# joyAnalog.net
KiCad netlist of a schematic drawn in EAGLE
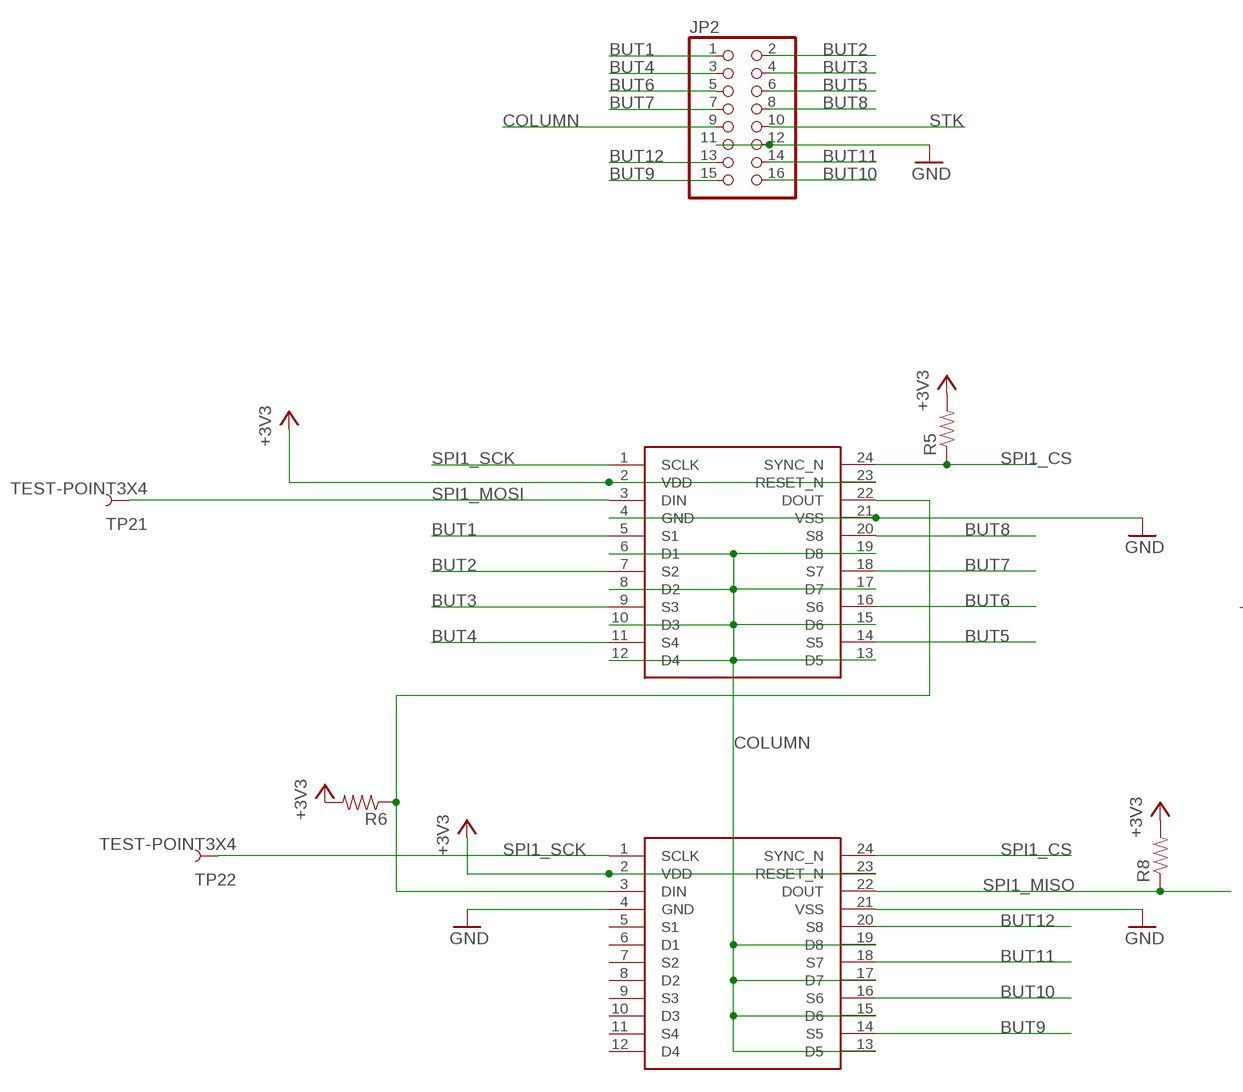
[diagram p0: schematic, sheet 1, part 1 of 2]
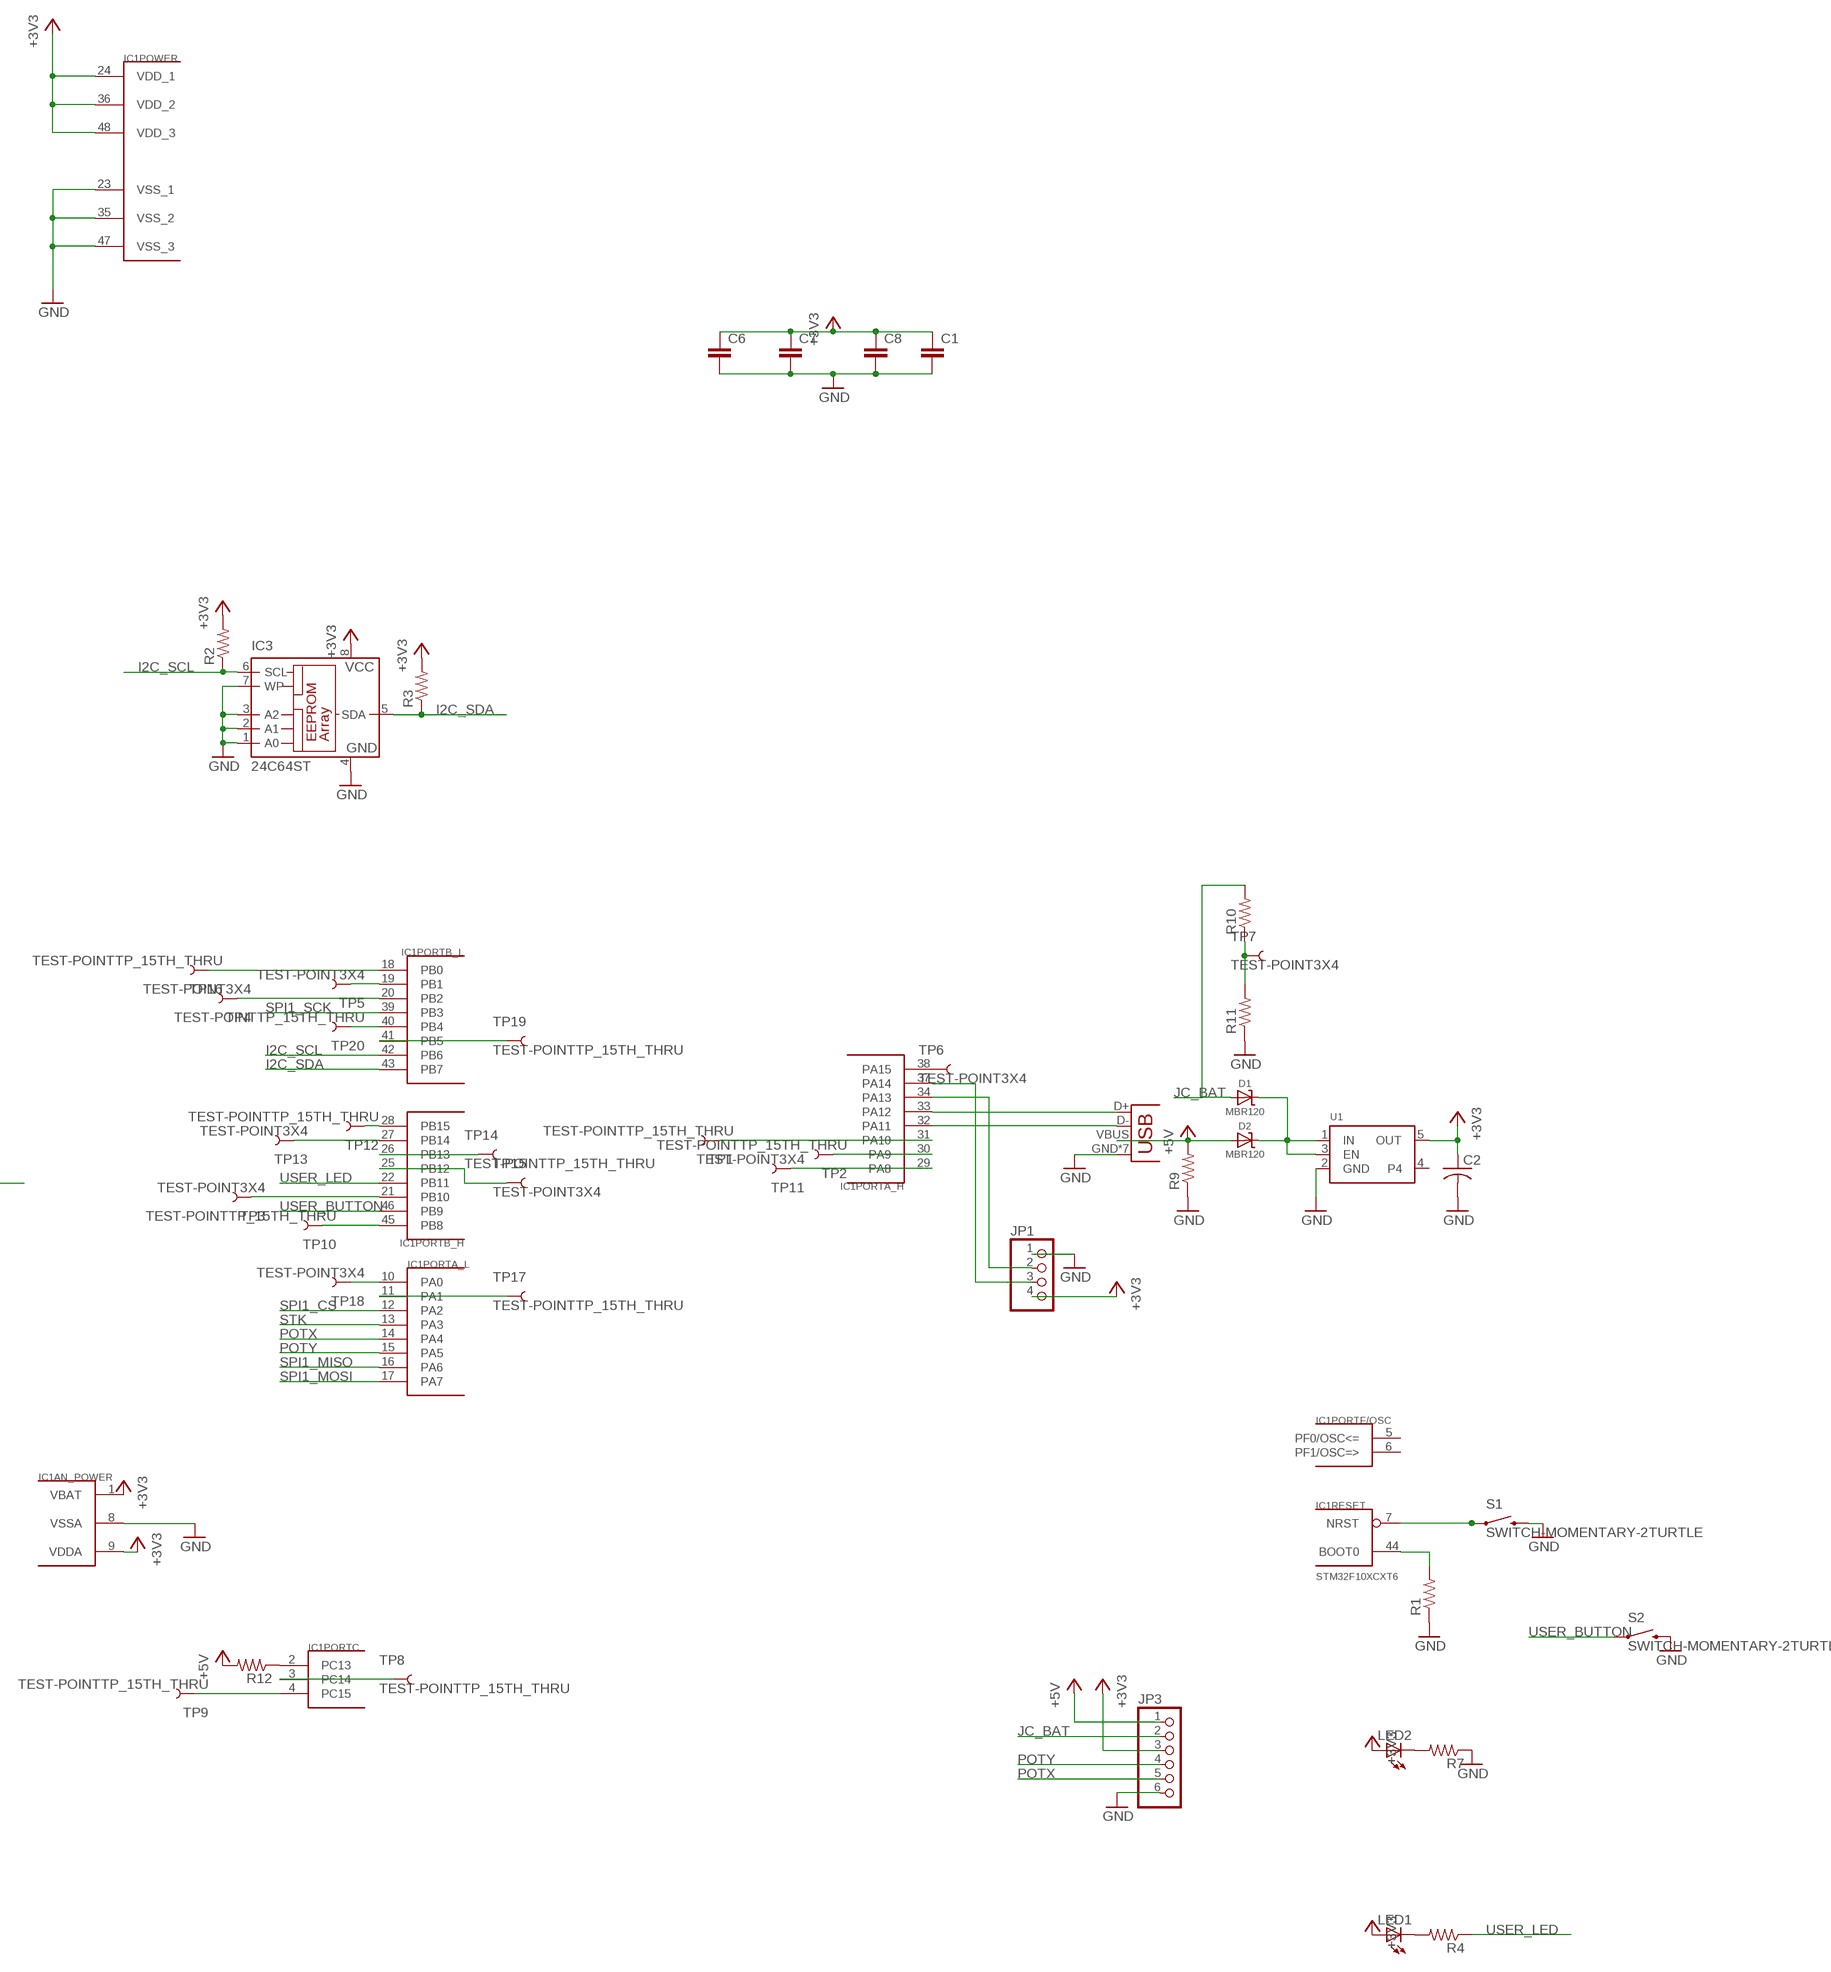
[diagram p1: schematic, sheet 1, part 2 of 2]

(export (version "E")
  (design (tool "Eeschema 10.0.6"))
  (components
    (comp (ref "C1")
      (value "CAP0805")
      (footprint "eagle-import:0805")
      (libsource (lib "eagle-import") (part "CAP0805"))
    )
    (comp (ref "C2")
      (value "C-USC1210")
      (footprint "eagle-import:C1210")
      (libsource (lib "eagle-import") (part "C-USC1210"))
    )
    (comp (ref "C6")
      (value "CAP0805")
      (footprint "eagle-import:0805")
      (libsource (lib "eagle-import") (part "CAP0805"))
    )
    (comp (ref "C7")
      (value "CAP0805")
      (footprint "eagle-import:0805")
      (libsource (lib "eagle-import") (part "CAP0805"))
    )
    (comp (ref "C8")
      (value "CAP0805")
      (footprint "eagle-import:0805")
      (libsource (lib "eagle-import") (part "CAP0805"))
    )
    (comp (ref "D1")
      (value "MBR120")
      (footprint "eagle-import:SOD-123")
      (libsource (lib "eagle-import") (part "DIODE-SCHOTTKYSOD-123"))
    )
    (comp (ref "D2")
      (value "MBR120")
      (footprint "eagle-import:SOD-123")
      (libsource (lib "eagle-import") (part "DIODE-SCHOTTKYSOD-123"))
    )
    (comp (ref "IC1")
      (value "STM32F10XCXT6")
      (footprint "eagle-import:TQFP48")
      (libsource (lib "eagle-import") (part "STM32F10XCXT6"))
    )
    (comp (ref "IC3")
      (value "24C64ST")
      (footprint "eagle-import:TSSOP8")
      (fields (field (name "MPN") "CAT24C64YI-GT3"))
      (libsource (lib "eagle-import") (part "24STC64"))
    )
    (comp (ref "JP1")
      (value "PINHD-1X4")
      (footprint "eagle-import:1X04")
      (libsource (lib "eagle-import") (part "PINHD-1X4"))
    )
    (comp (ref "JP2")
      (value "PINHD-2X8")
      (footprint "eagle-import:2X08")
      (libsource (lib "eagle-import") (part "PINHD-2X8"))
    )
    (comp (ref "JP3")
      (value "PINHD-1X6CB")
      (footprint "eagle-import:1X06-CLEANBIG")
      (libsource (lib "eagle-import") (part "PINHD-1X6CB"))
    )
    (comp (ref "LED1")
      (value "LEDCHIP-LED0805")
      (footprint "eagle-import:CHIP-LED0805")
      (libsource (lib "eagle-import") (part "LEDCHIP-LED0805"))
    )
    (comp (ref "LED2")
      (value "LEDCHIP-LED0805")
      (footprint "eagle-import:CHIP-LED0805")
      (libsource (lib "eagle-import") (part "LEDCHIP-LED0805"))
    )
    (comp (ref "R1")
      (value "RESISTOR0805-RES")
      (footprint "eagle-import:0805")
      (libsource (lib "eagle-import") (part "RESISTOR0805-RES"))
    )
    (comp (ref "R2")
      (value "RESISTOR0805-RES")
      (footprint "eagle-import:0805")
      (libsource (lib "eagle-import") (part "RESISTOR0805-RES"))
    )
    (comp (ref "R3")
      (value "RESISTOR0805-RES")
      (footprint "eagle-import:0805")
      (libsource (lib "eagle-import") (part "RESISTOR0805-RES"))
    )
    (comp (ref "R4")
      (value "RESISTOR0805-RES")
      (footprint "eagle-import:0805")
      (libsource (lib "eagle-import") (part "RESISTOR0805-RES"))
    )
    (comp (ref "R5")
      (value "RESISTOR0805-RES")
      (footprint "eagle-import:0805")
      (libsource (lib "eagle-import") (part "RESISTOR0805-RES"))
    )
    (comp (ref "R6")
      (value "RESISTOR0805-RES")
      (footprint "eagle-import:0805")
      (libsource (lib "eagle-import") (part "RESISTOR0805-RES"))
    )
    (comp (ref "R7")
      (value "RESISTOR0805-RES")
      (footprint "eagle-import:0805")
      (libsource (lib "eagle-import") (part "RESISTOR0805-RES"))
    )
    (comp (ref "R8")
      (value "RESISTOR0805-RES")
      (footprint "eagle-import:0805")
      (libsource (lib "eagle-import") (part "RESISTOR0805-RES"))
    )
    (comp (ref "R9")
      (value "RESISTOR0805-RES")
      (footprint "eagle-import:0805")
      (libsource (lib "eagle-import") (part "RESISTOR0805-RES"))
    )
    (comp (ref "R10")
      (value "RESISTOR0805-RES")
      (footprint "eagle-import:0805")
      (libsource (lib "eagle-import") (part "RESISTOR0805-RES"))
    )
    (comp (ref "R11")
      (value "RESISTOR0805-RES")
      (footprint "eagle-import:0805")
      (libsource (lib "eagle-import") (part "RESISTOR0805-RES"))
    )
    (comp (ref "R12")
      (value "RESISTOR0805-RES")
      (footprint "eagle-import:0805")
      (libsource (lib "eagle-import") (part "RESISTOR0805-RES"))
    )
    (comp (ref "S1")
      (value "SWITCH-MOMENTARY-2TURTLE")
      (footprint "eagle-import:KMR2")
      (libsource (lib "eagle-import") (part "SWITCH-MOMENTARY-2TURTLE"))
    )
    (comp (ref "S2")
      (value "SWITCH-MOMENTARY-2TURTLE")
      (footprint "eagle-import:KMR2")
      (libsource (lib "eagle-import") (part "SWITCH-MOMENTARY-2TURTLE"))
    )
    (comp (ref "TP1")
      (value "TEST-POINTTP_15TH_THRU")
      (footprint "eagle-import:TP_15TH")
      (libsource (lib "eagle-import") (part "pth testpoint_TEST-POINTTP_15TH_THRU"))
    )
    (comp (ref "TP2")
      (value "TEST-POINTTP_15TH_THRU")
      (footprint "eagle-import:TP_15TH")
      (libsource (lib "eagle-import") (part "pth testpoint_TEST-POINTTP_15TH_THRU"))
    )
    (comp (ref "TP3")
      (value "TEST-POINT3X4")
      (footprint "eagle-import:PAD.03X.04")
      (libsource (lib "eagle-import") (part "TEST-POINT3X4"))
    )
    (comp (ref "TP4")
      (value "TEST-POINT3X4")
      (footprint "eagle-import:PAD.03X.04")
      (libsource (lib "eagle-import") (part "TEST-POINT3X4"))
    )
    (comp (ref "TP5")
      (value "TEST-POINT3X4")
      (footprint "eagle-import:PAD.03X.04")
      (libsource (lib "eagle-import") (part "TEST-POINT3X4"))
    )
    (comp (ref "TP6")
      (value "TEST-POINT3X4")
      (footprint "eagle-import:PAD.03X.04")
      (libsource (lib "eagle-import") (part "TEST-POINT3X4"))
    )
    (comp (ref "TP7")
      (value "TEST-POINT3X4")
      (footprint "eagle-import:PAD.03X.04")
      (libsource (lib "eagle-import") (part "TEST-POINT3X4"))
    )
    (comp (ref "TP8")
      (value "TEST-POINTTP_15TH_THRU")
      (footprint "eagle-import:TP_15TH")
      (libsource (lib "eagle-import") (part "pth testpoint_TEST-POINTTP_15TH_THRU"))
    )
    (comp (ref "TP9")
      (value "TEST-POINTTP_15TH_THRU")
      (footprint "eagle-import:TP_15TH")
      (libsource (lib "eagle-import") (part "pth testpoint_TEST-POINTTP_15TH_THRU"))
    )
    (comp (ref "TP10")
      (value "TEST-POINTTP_15TH_THRU")
      (footprint "eagle-import:TP_15TH")
      (libsource (lib "eagle-import") (part "pth testpoint_TEST-POINTTP_15TH_THRU"))
    )
    (comp (ref "TP11")
      (value "TEST-POINT3X4")
      (footprint "eagle-import:PAD.03X.04")
      (libsource (lib "eagle-import") (part "TEST-POINT3X4"))
    )
    (comp (ref "TP12")
      (value "TEST-POINTTP_15TH_THRU")
      (footprint "eagle-import:TP_15TH")
      (libsource (lib "eagle-import") (part "pth testpoint_TEST-POINTTP_15TH_THRU"))
    )
    (comp (ref "TP13")
      (value "TEST-POINT3X4")
      (footprint "eagle-import:PAD.03X.04")
      (libsource (lib "eagle-import") (part "TEST-POINT3X4"))
    )
    (comp (ref "TP14")
      (value "TEST-POINTTP_15TH_THRU")
      (footprint "eagle-import:TP_15TH")
      (libsource (lib "eagle-import") (part "pth testpoint_TEST-POINTTP_15TH_THRU"))
    )
    (comp (ref "TP15")
      (value "TEST-POINT3X4")
      (footprint "eagle-import:PAD.03X.04")
      (libsource (lib "eagle-import") (part "TEST-POINT3X4"))
    )
    (comp (ref "TP16")
      (value "TEST-POINTTP_15TH_THRU")
      (footprint "eagle-import:TP_15TH")
      (libsource (lib "eagle-import") (part "pth testpoint_TEST-POINTTP_15TH_THRU"))
    )
    (comp (ref "TP17")
      (value "TEST-POINTTP_15TH_THRU")
      (footprint "eagle-import:TP_15TH")
      (libsource (lib "eagle-import") (part "pth testpoint_TEST-POINTTP_15TH_THRU"))
    )
    (comp (ref "TP18")
      (value "TEST-POINT3X4")
      (footprint "eagle-import:PAD.03X.04")
      (libsource (lib "eagle-import") (part "TEST-POINT3X4"))
    )
    (comp (ref "TP19")
      (value "TEST-POINTTP_15TH_THRU")
      (footprint "eagle-import:TP_15TH")
      (libsource (lib "eagle-import") (part "pth testpoint_TEST-POINTTP_15TH_THRU"))
    )
    (comp (ref "TP20")
      (value "TEST-POINTTP_15TH_THRU")
      (footprint "eagle-import:TP_15TH")
      (libsource (lib "eagle-import") (part "pth testpoint_TEST-POINTTP_15TH_THRU"))
    )
    (comp (ref "TP21")
      (value "TEST-POINT3X4")
      (footprint "eagle-import:PAD.03X.04")
      (libsource (lib "eagle-import") (part "TEST-POINT3X4"))
    )
    (comp (ref "TP22")
      (value "TEST-POINT3X4")
      (footprint "eagle-import:PAD.03X.04")
      (libsource (lib "eagle-import") (part "TEST-POINT3X4"))
    )
    (comp (ref "U$3")
      (value "ADG714_DEV")
      (footprint "eagle-import:TSSOP-24")
      (libsource (lib "eagle-import") (part "ADG714_DEV"))
    )
    (comp (ref "U$4")
      (value "ADG714_DEV")
      (footprint "eagle-import:TSSOP-24")
      (libsource (lib "eagle-import") (part "ADG714_DEV"))
    )
    (comp (ref "U1")
      (value "VREG_SOT23-5")
      (footprint "eagle-import:SOT23-5")
      (libsource (lib "eagle-import") (part "VREG_SOT23-5"))
    )
    (comp (ref "X1")
      (value "USB-MICROB")
      (footprint "eagle-import:USB-MICROB")
      (libsource (lib "eagle-import") (part "USB-MICROB"))
    )
  )
  (nets
    (net (code "1") (name "+3V3") (class "Default")
      (node (ref "C1") (pin "1") (pinfunction "1_1") (pintype "passive"))
      (node (ref "C2") (pin "1") (pinfunction "1_1") (pintype "passive"))
      (node (ref "C6") (pin "1") (pinfunction "1_1") (pintype "passive"))
      (node (ref "C7") (pin "1") (pinfunction "1_1") (pintype "passive"))
      (node (ref "C8") (pin "1") (pinfunction "1_1") (pintype "passive"))
      (node (ref "IC1") (pin "1") (pinfunction "VBAT_1") (pintype "power_in"))
      (node (ref "IC1") (pin "24") (pinfunction "VDD_1_24") (pintype "power_in"))
      (node (ref "IC1") (pin "36") (pinfunction "VDD_2_36") (pintype "power_in"))
      (node (ref "IC1") (pin "48") (pinfunction "VDD_3_48") (pintype "power_in"))
      (node (ref "IC1") (pin "9") (pinfunction "VDDA_9") (pintype "power_in"))
      (node (ref "IC3") (pin "8") (pinfunction "VCC_8") (pintype "power_in"))
      (node (ref "JP1") (pin "4") (pinfunction "4_4") (pintype "passive"))
      (node (ref "JP3") (pin "3") (pinfunction "3_3") (pintype "passive"))
      (node (ref "LED1") (pin "A") (pinfunction "A_A") (pintype "passive"))
      (node (ref "LED2") (pin "A") (pinfunction "A_A") (pintype "passive"))
      (node (ref "R2") (pin "2") (pinfunction "2_2") (pintype "passive"))
      (node (ref "R3") (pin "2") (pinfunction "2_2") (pintype "passive"))
      (node (ref "R5") (pin "2") (pinfunction "2_2") (pintype "passive"))
      (node (ref "R6") (pin "2") (pinfunction "2_2") (pintype "passive"))
      (node (ref "R8") (pin "2") (pinfunction "2_2") (pintype "passive"))
      (node (ref "U$3") (pin "2") (pinfunction "VDD_2") (pintype "bidirectional"))
      (node (ref "U$3") (pin "23") (pinfunction "RESET_N_23") (pintype "bidirectional"))
      (node (ref "U$4") (pin "2") (pinfunction "VDD_2") (pintype "bidirectional"))
      (node (ref "U$4") (pin "23") (pinfunction "RESET_N_23") (pintype "bidirectional"))
      (node (ref "U1") (pin "5") (pinfunction "OUT_5") (pintype "power_in"))
    )
    (net (code "2") (name "+5V") (class "Default")
      (node (ref "D2") (pin "A") (pinfunction "A_A") (pintype "passive"))
      (node (ref "JP3") (pin "1") (pinfunction "1_1") (pintype "passive"))
      (node (ref "R12") (pin "2") (pinfunction "2_2") (pintype "passive"))
      (node (ref "R9") (pin "2") (pinfunction "2_2") (pintype "passive"))
      (node (ref "X1") (pin "VBUS") (pinfunction "VBUS_VBUS") (pintype "bidirectional"))
    )
    (net (code "3") (name "/BUT1") (class "Default")
      (node (ref "JP2") (pin "1") (pinfunction "1_1") (pintype "passive"))
      (node (ref "U$3") (pin "5") (pinfunction "S1_5") (pintype "bidirectional"))
    )
    (net (code "4") (name "/BUT2") (class "Default")
      (node (ref "JP2") (pin "2") (pinfunction "2_2") (pintype "passive"))
      (node (ref "U$3") (pin "7") (pinfunction "S2_7") (pintype "bidirectional"))
    )
    (net (code "5") (name "/BUT3") (class "Default")
      (node (ref "JP2") (pin "4") (pinfunction "4_4") (pintype "passive"))
      (node (ref "U$3") (pin "9") (pinfunction "S3_9") (pintype "bidirectional"))
    )
    (net (code "6") (name "/BUT4") (class "Default")
      (node (ref "JP2") (pin "3") (pinfunction "3_3") (pintype "passive"))
      (node (ref "U$3") (pin "11") (pinfunction "S4_11") (pintype "bidirectional"))
    )
    (net (code "7") (name "/BUT5") (class "Default")
      (node (ref "JP2") (pin "6") (pinfunction "6_6") (pintype "passive"))
      (node (ref "U$3") (pin "14") (pinfunction "S5_14") (pintype "bidirectional"))
    )
    (net (code "8") (name "/BUT6") (class "Default")
      (node (ref "JP2") (pin "5") (pinfunction "5_5") (pintype "passive"))
      (node (ref "U$3") (pin "16") (pinfunction "S6_16") (pintype "bidirectional"))
    )
    (net (code "9") (name "/BUT7") (class "Default")
      (node (ref "JP2") (pin "7") (pinfunction "7_7") (pintype "passive"))
      (node (ref "U$3") (pin "18") (pinfunction "S7_18") (pintype "bidirectional"))
    )
    (net (code "10") (name "/BUT8") (class "Default")
      (node (ref "JP2") (pin "8") (pinfunction "8_8") (pintype "passive"))
      (node (ref "U$3") (pin "20") (pinfunction "S8_20") (pintype "bidirectional"))
    )
    (net (code "11") (name "/BUT9") (class "Default")
      (node (ref "JP2") (pin "15") (pinfunction "15_15") (pintype "passive"))
      (node (ref "U$4") (pin "14") (pinfunction "S5_14") (pintype "bidirectional"))
    )
    (net (code "12") (name "/BUT10") (class "Default")
      (node (ref "JP2") (pin "16") (pinfunction "16_16") (pintype "passive"))
      (node (ref "U$4") (pin "16") (pinfunction "S6_16") (pintype "bidirectional"))
    )
    (net (code "13") (name "/BUT11") (class "Default")
      (node (ref "JP2") (pin "14") (pinfunction "14_14") (pintype "passive"))
      (node (ref "U$4") (pin "18") (pinfunction "S7_18") (pintype "bidirectional"))
    )
    (net (code "14") (name "/BUT12") (class "Default")
      (node (ref "JP2") (pin "13") (pinfunction "13_13") (pintype "passive"))
      (node (ref "U$4") (pin "20") (pinfunction "S8_20") (pintype "bidirectional"))
    )
    (net (code "15") (name "/COLUMN") (class "Default")
      (node (ref "JP2") (pin "9") (pinfunction "9_9") (pintype "passive"))
      (node (ref "U$3") (pin "10") (pinfunction "D3_10") (pintype "bidirectional"))
      (node (ref "U$3") (pin "12") (pinfunction "D4_12") (pintype "bidirectional"))
      (node (ref "U$3") (pin "13") (pinfunction "D5_13") (pintype "bidirectional"))
      (node (ref "U$3") (pin "15") (pinfunction "D6_15") (pintype "bidirectional"))
      (node (ref "U$3") (pin "17") (pinfunction "D7_17") (pintype "bidirectional"))
      (node (ref "U$3") (pin "19") (pinfunction "D8_19") (pintype "bidirectional"))
      (node (ref "U$3") (pin "6") (pinfunction "D1_6") (pintype "bidirectional"))
      (node (ref "U$3") (pin "8") (pinfunction "D2_8") (pintype "bidirectional"))
      (node (ref "U$4") (pin "13") (pinfunction "D5_13") (pintype "bidirectional"))
      (node (ref "U$4") (pin "15") (pinfunction "D6_15") (pintype "bidirectional"))
      (node (ref "U$4") (pin "17") (pinfunction "D7_17") (pintype "bidirectional"))
      (node (ref "U$4") (pin "19") (pinfunction "D8_19") (pintype "bidirectional"))
    )
    (net (code "16") (name "/I2C_SCL") (class "Default")
      (node (ref "IC1") (pin "42") (pinfunction "PB6_42") (pintype "bidirectional"))
      (node (ref "IC3") (pin "6") (pinfunction "SCL_6") (pintype "input"))
      (node (ref "R2") (pin "1") (pinfunction "1_1") (pintype "passive"))
    )
    (net (code "17") (name "/I2C_SDA") (class "Default")
      (node (ref "IC1") (pin "43") (pinfunction "PB7_43") (pintype "bidirectional"))
      (node (ref "IC3") (pin "5") (pinfunction "SDA_5") (pintype "bidirectional"))
      (node (ref "R3") (pin "1") (pinfunction "1_1") (pintype "passive"))
    )
    (net (code "18") (name "/JC_BAT") (class "Default")
      (node (ref "D1") (pin "A") (pinfunction "A_A") (pintype "passive"))
      (node (ref "JP3") (pin "2") (pinfunction "2_2") (pintype "passive"))
      (node (ref "R10") (pin "2") (pinfunction "2_2") (pintype "passive"))
    )
    (net (code "19") (name "/POTX") (class "Default")
      (node (ref "IC1") (pin "14") (pinfunction "PA4_14") (pintype "bidirectional"))
      (node (ref "JP3") (pin "5") (pinfunction "5_5") (pintype "passive"))
    )
    (net (code "20") (name "/POTY") (class "Default")
      (node (ref "IC1") (pin "15") (pinfunction "PA5_15") (pintype "bidirectional"))
      (node (ref "JP3") (pin "4") (pinfunction "4_4") (pintype "passive"))
    )
    (net (code "21") (name "/SPI1_CS") (class "Default")
      (node (ref "IC1") (pin "12") (pinfunction "PA2_12") (pintype "bidirectional"))
      (node (ref "R5") (pin "1") (pinfunction "1_1") (pintype "passive"))
      (node (ref "U$3") (pin "24") (pinfunction "SYNC_N_24") (pintype "bidirectional"))
      (node (ref "U$4") (pin "24") (pinfunction "SYNC_N_24") (pintype "bidirectional"))
    )
    (net (code "22") (name "/SPI1_MISO") (class "Default")
      (node (ref "IC1") (pin "16") (pinfunction "PA6_16") (pintype "bidirectional"))
      (node (ref "R8") (pin "1") (pinfunction "1_1") (pintype "passive"))
      (node (ref "U$4") (pin "22") (pinfunction "DOUT_22") (pintype "bidirectional"))
    )
    (net (code "23") (name "/SPI1_MOSI") (class "Default")
      (node (ref "IC1") (pin "17") (pinfunction "PA7_17") (pintype "bidirectional"))
      (node (ref "TP21") (pin "P$1") (pinfunction "1_P$1") (pintype "bidirectional"))
      (node (ref "U$3") (pin "3") (pinfunction "DIN_3") (pintype "bidirectional"))
    )
    (net (code "24") (name "/SPI1_SCK") (class "Default")
      (node (ref "IC1") (pin "39") (pinfunction "PB3_39") (pintype "bidirectional"))
      (node (ref "TP22") (pin "P$1") (pinfunction "1_P$1") (pintype "bidirectional"))
      (node (ref "U$3") (pin "1") (pinfunction "SCLK_1") (pintype "bidirectional"))
      (node (ref "U$4") (pin "1") (pinfunction "SCLK_1") (pintype "bidirectional"))
    )
    (net (code "25") (name "/STK") (class "Default")
      (node (ref "IC1") (pin "13") (pinfunction "PA3_13") (pintype "bidirectional"))
      (node (ref "JP2") (pin "10") (pinfunction "10_10") (pintype "passive"))
    )
    (net (code "26") (name "/USER_BUTTON") (class "Default")
      (node (ref "IC1") (pin "46") (pinfunction "PB9_46") (pintype "bidirectional"))
      (node (ref "S2") (pin "1") (pinfunction "1_1") (pintype "passive"))
    )
    (net (code "27") (name "/USER_LED") (class "Default")
      (node (ref "IC1") (pin "22") (pinfunction "PB11_22") (pintype "bidirectional"))
      (node (ref "R4") (pin "1") (pinfunction "1_1") (pintype "passive"))
    )
    (net (code "28") (name "GND") (class "Default")
      (node (ref "C1") (pin "2") (pinfunction "2_2") (pintype "passive"))
      (node (ref "C2") (pin "2") (pinfunction "2_2") (pintype "passive"))
      (node (ref "C6") (pin "2") (pinfunction "2_2") (pintype "passive"))
      (node (ref "C7") (pin "2") (pinfunction "2_2") (pintype "passive"))
      (node (ref "C8") (pin "2") (pinfunction "2_2") (pintype "passive"))
      (node (ref "IC1") (pin "23") (pinfunction "VSS_1_23") (pintype "power_in"))
      (node (ref "IC1") (pin "35") (pinfunction "VSS_2_35") (pintype "power_in"))
      (node (ref "IC1") (pin "47") (pinfunction "VSS_3_47") (pintype "power_in"))
      (node (ref "IC1") (pin "8") (pinfunction "VSSA_8") (pintype "power_in"))
      (node (ref "IC3") (pin "1") (pinfunction "A0_1") (pintype "input"))
      (node (ref "IC3") (pin "2") (pinfunction "A1_2") (pintype "input"))
      (node (ref "IC3") (pin "3") (pinfunction "A2_3") (pintype "input"))
      (node (ref "IC3") (pin "4") (pinfunction "GND_4") (pintype "power_in"))
      (node (ref "IC3") (pin "7") (pinfunction "WP_7") (pintype "input"))
      (node (ref "JP1") (pin "1") (pinfunction "1_1") (pintype "passive"))
      (node (ref "JP2") (pin "11") (pinfunction "11_11") (pintype "passive"))
      (node (ref "JP2") (pin "12") (pinfunction "12_12") (pintype "passive"))
      (node (ref "JP3") (pin "6") (pinfunction "6_6") (pintype "passive"))
      (node (ref "R1") (pin "1") (pinfunction "1_1") (pintype "passive"))
      (node (ref "R11") (pin "1") (pinfunction "1_1") (pintype "passive"))
      (node (ref "R7") (pin "1") (pinfunction "1_1") (pintype "passive"))
      (node (ref "R9") (pin "1") (pinfunction "1_1") (pintype "passive"))
      (node (ref "S1") (pin "3") (pinfunction "2_3") (pintype "passive"))
      (node (ref "S2") (pin "3") (pinfunction "2_3") (pintype "passive"))
      (node (ref "U$3") (pin "21") (pinfunction "VSS_21") (pintype "bidirectional"))
      (node (ref "U$3") (pin "4") (pinfunction "GND_4") (pintype "bidirectional"))
      (node (ref "U$4") (pin "21") (pinfunction "VSS_21") (pintype "bidirectional"))
      (node (ref "U$4") (pin "4") (pinfunction "GND_4") (pintype "bidirectional"))
      (node (ref "U1") (pin "2") (pinfunction "GND_2") (pintype "power_in"))
      (node (ref "X1") (pin "GND") (pinfunction "GND_GND") (pintype "bidirectional"))
      (node (ref "X1") (pin "P1") (pinfunction "GND_P1") (pintype "bidirectional"))
      (node (ref "X1") (pin "P2") (pinfunction "GND_P2") (pintype "bidirectional"))
      (node (ref "X1") (pin "P3") (pinfunction "GND_P3") (pintype "bidirectional"))
      (node (ref "X1") (pin "P4") (pinfunction "GND_P4") (pintype "bidirectional"))
      (node (ref "X1") (pin "P5") (pinfunction "GND_P5") (pintype "bidirectional"))
      (node (ref "X1") (pin "P6") (pinfunction "GND_P6") (pintype "bidirectional"))
    )
    (net (code "29") (name "Net-(IC1B-PA8)") (class "Default")
      (node (ref "IC1") (pin "29") (pinfunction "PA8_29") (pintype "bidirectional"))
      (node (ref "TP11") (pin "P$1") (pinfunction "1_P$1") (pintype "bidirectional"))
    )
    (net (code "30") (name "Net-(IC1B-PA9)") (class "Default")
      (node (ref "IC1") (pin "30") (pinfunction "PA9_30") (pintype "bidirectional"))
      (node (ref "TP2") (pin "P$1") (pinfunction "1_P$1") (pintype "bidirectional"))
    )
    (net (code "31") (name "Net-(IC1B-PA10)") (class "Default")
      (node (ref "IC1") (pin "31") (pinfunction "PA10_31") (pintype "bidirectional"))
      (node (ref "TP1") (pin "P$1") (pinfunction "1_P$1") (pintype "bidirectional"))
    )
    (net (code "32") (name "Net-(IC1B-PA11)") (class "Default")
      (node (ref "IC1") (pin "32") (pinfunction "PA11_32") (pintype "bidirectional"))
      (node (ref "X1") (pin "D-") (pinfunction "D-_D-") (pintype "bidirectional"))
    )
    (net (code "33") (name "Net-(IC1B-PA12)") (class "Default")
      (node (ref "IC1") (pin "33") (pinfunction "PA12_33") (pintype "bidirectional"))
      (node (ref "X1") (pin "D+") (pinfunction "D+_D+") (pintype "bidirectional"))
    )
    (net (code "34") (name "Net-(IC1B-PA13)") (class "Default")
      (node (ref "IC1") (pin "34") (pinfunction "PA13_34") (pintype "bidirectional"))
      (node (ref "JP1") (pin "2") (pinfunction "2_2") (pintype "passive"))
    )
    (net (code "35") (name "Net-(IC1B-PA14)") (class "Default")
      (node (ref "IC1") (pin "37") (pinfunction "PA14_37") (pintype "bidirectional"))
      (node (ref "JP1") (pin "3") (pinfunction "3_3") (pintype "passive"))
    )
    (net (code "36") (name "Net-(IC1B-PA15)") (class "Default")
      (node (ref "IC1") (pin "38") (pinfunction "PA15_38") (pintype "bidirectional"))
      (node (ref "TP6") (pin "P$1") (pinfunction "1_P$1") (pintype "bidirectional"))
    )
    (net (code "37") (name "Net-(IC1C-PA0)") (class "Default")
      (node (ref "IC1") (pin "10") (pinfunction "PA0_10") (pintype "bidirectional"))
      (node (ref "TP18") (pin "P$1") (pinfunction "1_P$1") (pintype "bidirectional"))
    )
    (net (code "38") (name "Net-(IC1C-PA1)") (class "Default")
      (node (ref "IC1") (pin "11") (pinfunction "PA1_11") (pintype "bidirectional"))
      (node (ref "TP17") (pin "P$1") (pinfunction "1_P$1") (pintype "bidirectional"))
    )
    (net (code "39") (name "Net-(IC1D-PB8)") (class "Default")
      (node (ref "IC1") (pin "45") (pinfunction "PB8_45") (pintype "bidirectional"))
      (node (ref "TP10") (pin "P$1") (pinfunction "1_P$1") (pintype "bidirectional"))
    )
    (net (code "40") (name "Net-(IC1D-PB10)") (class "Default")
      (node (ref "IC1") (pin "21") (pinfunction "PB10_21") (pintype "bidirectional"))
      (node (ref "TP3") (pin "P$1") (pinfunction "1_P$1") (pintype "bidirectional"))
    )
    (net (code "41") (name "Net-(IC1D-PB12)") (class "Default")
      (node (ref "IC1") (pin "25") (pinfunction "PB12_25") (pintype "bidirectional"))
      (node (ref "TP15") (pin "P$1") (pinfunction "1_P$1") (pintype "bidirectional"))
    )
    (net (code "42") (name "Net-(IC1D-PB13)") (class "Default")
      (node (ref "IC1") (pin "26") (pinfunction "PB13_26") (pintype "bidirectional"))
      (node (ref "TP14") (pin "P$1") (pinfunction "1_P$1") (pintype "bidirectional"))
    )
    (net (code "43") (name "Net-(IC1D-PB14)") (class "Default")
      (node (ref "IC1") (pin "27") (pinfunction "PB14_27") (pintype "bidirectional"))
      (node (ref "TP13") (pin "P$1") (pinfunction "1_P$1") (pintype "bidirectional"))
    )
    (net (code "44") (name "Net-(IC1D-PB15)") (class "Default")
      (node (ref "IC1") (pin "28") (pinfunction "PB15_28") (pintype "bidirectional"))
      (node (ref "TP12") (pin "P$1") (pinfunction "1_P$1") (pintype "bidirectional"))
    )
    (net (code "45") (name "Net-(IC1E-PB0)") (class "Default")
      (node (ref "IC1") (pin "18") (pinfunction "PB0_18") (pintype "bidirectional"))
      (node (ref "TP16") (pin "P$1") (pinfunction "1_P$1") (pintype "bidirectional"))
    )
    (net (code "46") (name "Net-(IC1E-PB1)") (class "Default")
      (node (ref "IC1") (pin "19") (pinfunction "PB1_19") (pintype "bidirectional"))
      (node (ref "TP5") (pin "P$1") (pinfunction "1_P$1") (pintype "bidirectional"))
    )
    (net (code "47") (name "Net-(IC1E-PB2)") (class "Default")
      (node (ref "IC1") (pin "20") (pinfunction "PB2_20") (pintype "bidirectional"))
      (node (ref "TP4") (pin "P$1") (pinfunction "1_P$1") (pintype "bidirectional"))
    )
    (net (code "48") (name "Net-(IC1E-PB4)") (class "Default")
      (node (ref "IC1") (pin "40") (pinfunction "PB4_40") (pintype "bidirectional"))
      (node (ref "TP20") (pin "P$1") (pinfunction "1_P$1") (pintype "bidirectional"))
    )
    (net (code "49") (name "Net-(IC1E-PB5)") (class "Default")
      (node (ref "IC1") (pin "41") (pinfunction "PB5_41") (pintype "bidirectional"))
      (node (ref "TP19") (pin "P$1") (pinfunction "1_P$1") (pintype "bidirectional"))
    )
    (net (code "50") (name "Net-(IC1F-PC13)") (class "Default")
      (node (ref "IC1") (pin "2") (pinfunction "PC13_2") (pintype "bidirectional"))
      (node (ref "R12") (pin "1") (pinfunction "1_1") (pintype "passive"))
    )
    (net (code "51") (name "Net-(IC1F-PC14)") (class "Default")
      (node (ref "IC1") (pin "3") (pinfunction "PC14_3") (pintype "bidirectional"))
      (node (ref "TP8") (pin "P$1") (pinfunction "1_P$1") (pintype "bidirectional"))
    )
    (net (code "52") (name "Net-(IC1F-PC15)") (class "Default")
      (node (ref "IC1") (pin "4") (pinfunction "PC15_4") (pintype "bidirectional"))
      (node (ref "TP9") (pin "P$1") (pinfunction "1_P$1") (pintype "bidirectional"))
    )
    (net (code "53") (name "Net-(IC1I-BOOT0)") (class "Default")
      (node (ref "IC1") (pin "44") (pinfunction "BOOT0_44") (pintype "input"))
      (node (ref "R1") (pin "2") (pinfunction "2_2") (pintype "passive"))
    )
    (net (code "54") (name "Net-(IC1I-NRST)") (class "Default")
      (node (ref "IC1") (pin "7") (pinfunction "NRST_7") (pintype "input"))
      (node (ref "S1") (pin "1") (pinfunction "1_1") (pintype "passive"))
    )
    (net (code "55") (name "Net-(LED1-PadC)") (class "Default")
      (node (ref "LED1") (pin "C") (pinfunction "C_C") (pintype "passive"))
      (node (ref "R4") (pin "2") (pinfunction "2_2") (pintype "passive"))
    )
    (net (code "56") (name "Net-(LED2-PadC)") (class "Default")
      (node (ref "LED2") (pin "C") (pinfunction "C_C") (pintype "passive"))
      (node (ref "R7") (pin "2") (pinfunction "2_2") (pintype "passive"))
    )
    (net (code "57") (name "Net-(TP7-1)") (class "Default")
      (node (ref "R10") (pin "1") (pinfunction "1_1") (pintype "passive"))
      (node (ref "R11") (pin "2") (pinfunction "2_2") (pintype "passive"))
      (node (ref "TP7") (pin "P$1") (pinfunction "1_P$1") (pintype "bidirectional"))
    )
    (net (code "58") (name "Net-(U$3-DOUT)") (class "Default")
      (node (ref "R6") (pin "1") (pinfunction "1_1") (pintype "passive"))
      (node (ref "U$3") (pin "22") (pinfunction "DOUT_22") (pintype "bidirectional"))
      (node (ref "U$4") (pin "3") (pinfunction "DIN_3") (pintype "bidirectional"))
    )
    (net (code "59") (name "Net-(U1-EN)") (class "Default")
      (node (ref "D1") (pin "C") (pinfunction "C_C") (pintype "passive"))
      (node (ref "D2") (pin "C") (pinfunction "C_C") (pintype "passive"))
      (node (ref "U1") (pin "1") (pinfunction "IN_1") (pintype "power_in"))
      (node (ref "U1") (pin "3") (pinfunction "EN_3") (pintype "input"))
    )
    (net (code "60") (name "unconnected-(IC1G-PF0{slash}OSC<=-Pad5)") (class "Default")
      (node (ref "IC1") (pin "5") (pinfunction "PF0/OSC<=_5") (pintype "bidirectional"))
    )
    (net (code "61") (name "unconnected-(IC1G-PF1{slash}OSC=>-Pad6)") (class "Default")
      (node (ref "IC1") (pin "6") (pinfunction "PF1/OSC=>_6") (pintype "bidirectional"))
    )
    (net (code "62") (name "unconnected-(U$4-D1-Pad6)") (class "Default")
      (node (ref "U$4") (pin "6") (pinfunction "D1_6") (pintype "bidirectional"))
    )
    (net (code "63") (name "unconnected-(U$4-D2-Pad8)") (class "Default")
      (node (ref "U$4") (pin "8") (pinfunction "D2_8") (pintype "bidirectional"))
    )
    (net (code "64") (name "unconnected-(U$4-D3-Pad10)") (class "Default")
      (node (ref "U$4") (pin "10") (pinfunction "D3_10") (pintype "bidirectional"))
    )
    (net (code "65") (name "unconnected-(U$4-D4-Pad12)") (class "Default")
      (node (ref "U$4") (pin "12") (pinfunction "D4_12") (pintype "bidirectional"))
    )
    (net (code "66") (name "unconnected-(U$4-S1-Pad5)") (class "Default")
      (node (ref "U$4") (pin "5") (pinfunction "S1_5") (pintype "bidirectional"))
    )
    (net (code "67") (name "unconnected-(U$4-S2-Pad7)") (class "Default")
      (node (ref "U$4") (pin "7") (pinfunction "S2_7") (pintype "bidirectional"))
    )
    (net (code "68") (name "unconnected-(U$4-S3-Pad9)") (class "Default")
      (node (ref "U$4") (pin "9") (pinfunction "S3_9") (pintype "bidirectional"))
    )
    (net (code "69") (name "unconnected-(U$4-S4-Pad11)") (class "Default")
      (node (ref "U$4") (pin "11") (pinfunction "S4_11") (pintype "bidirectional"))
    )
    (net (code "70") (name "unconnected-(U1-P4-Pad4)") (class "Default")
      (node (ref "U1") (pin "4") (pinfunction "P4_4") (pintype "bidirectional"))
    )
  )
)
